# STM_Preamplifier.net
KiCad netlist of a schematic drawn in EasyEDA Pro
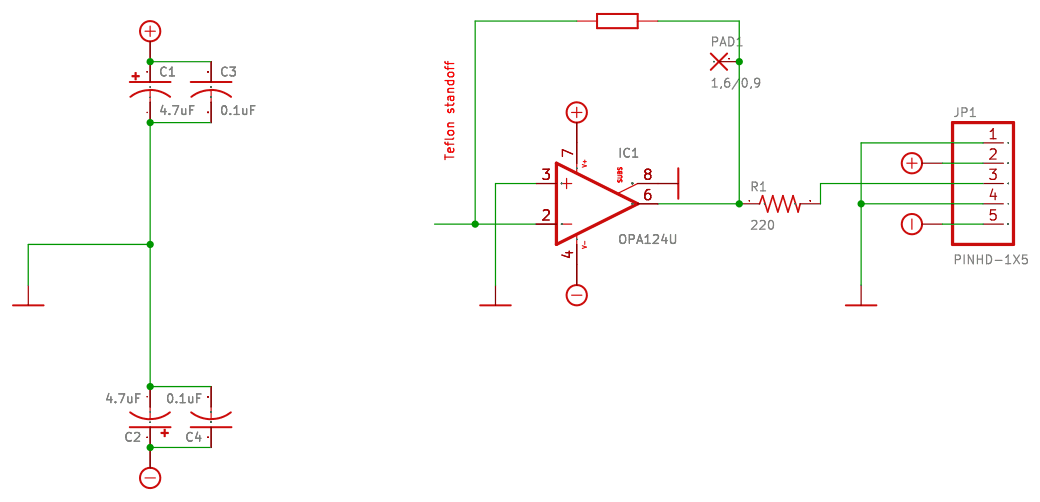
[diagram p0: schematic sheet]

(export (version "E")
  (design (tool "Eeschema 10.0.6"))
  (components
    (comp (ref "C1")
      (value "4.7uF")
      (footprint "easyedapro:C/6032-28W")
      (libsource (lib "easyedapro") (part "resistor_CPOL-US_C/6032-28W"))
    )
    (comp (ref "C2")
      (value "4.7uF")
      (footprint "easyedapro:C/6032-28W")
      (libsource (lib "easyedapro") (part "resistor_CPOL-US_C/6032-28W"))
    )
    (comp (ref "C3")
      (value "0.1uF")
      (footprint "easyedapro:C0603")
      (libsource (lib "easyedapro") (part "resistor_C-US_C0603"))
    )
    (comp (ref "C4")
      (value "0.1uF")
      (footprint "easyedapro:C0603")
      (libsource (lib "easyedapro") (part "resistor_C-US_C0603"))
    )
    (comp (ref "IC1")
      (value "OPA124U")
      (footprint "easyedapro:SO08")
      (libsource (lib "easyedapro") (part "burr-brown_OPA124U_"))
    )
    (comp (ref "JP1")
      (value "PINHD-1X5")
      (footprint "easyedapro:1X05")
      (libsource (lib "easyedapro") (part "pinhead_PINHD-1X5_"))
    )
    (comp (ref "PAD1")
      (value "1,6/0,9")
      (footprint "easyedapro:1,6/0,9")
      (libsource (lib "easyedapro") (part "wirepad_1,6/0,9_"))
    )
    (comp (ref "R1")
      (value "220")
      (footprint "easyedapro:R0603")
      (libsource (lib "easyedapro") (part "resistor_R-US__R0603"))
    )
    (comp (ref "R3") (value "100M") (libsource (lib "easyedapro") (part "docu-dummy_R_")))
  )
  (nets
    (net (code "1") (name "+9V") (class "Default")
      (node (ref "C1") (pin "+") (pinfunction "+_+") (pintype "unspecified"))
      (node (ref "C3") (pin "1") (pinfunction "1_1") (pintype "unspecified"))
      (node (ref "IC1") (pin "7") (pinfunction "V+_7") (pintype "unspecified"))
      (node (ref "JP1") (pin "2") (pinfunction "2_2") (pintype "unspecified"))
    )
    (net (code "2") (name "-9V") (class "Default")
      (node (ref "C2") (pin "+") (pinfunction "+_+") (pintype "unspecified"))
      (node (ref "C4") (pin "1") (pinfunction "1_1") (pintype "unspecified"))
      (node (ref "IC1") (pin "4") (pinfunction "V-_4") (pintype "unspecified"))
      (node (ref "JP1") (pin "5") (pinfunction "5_5") (pintype "unspecified"))
    )
    (net (code "3") (name "GND") (class "Default")
      (node (ref "C1") (pin "-") (pinfunction "-_-") (pintype "unspecified"))
      (node (ref "C2") (pin "-") (pinfunction "-_-") (pintype "unspecified"))
      (node (ref "C3") (pin "2") (pinfunction "2_2") (pintype "unspecified"))
      (node (ref "C4") (pin "2") (pinfunction "2_2") (pintype "unspecified"))
      (node (ref "IC1") (pin "3") (pinfunction "+IN_3") (pintype "input"))
      (node (ref "IC1") (pin "8") (pinfunction "SUBS_8") (pintype "unspecified"))
      (node (ref "JP1") (pin "1") (pinfunction "1_1") (pintype "unspecified"))
      (node (ref "JP1") (pin "4") (pinfunction "4_4") (pintype "unspecified"))
    )
    (net (code "4") (name "Net-(IC1-OUT)") (class "Default")
      (node (ref "IC1") (pin "6") (pinfunction "OUT_6") (pintype "output"))
      (node (ref "PAD1") (pin "1") (pinfunction "P_1") (pintype "unspecified"))
      (node (ref "R1") (pin "1") (pinfunction "1_1") (pintype "unspecified"))
    )
    (net (code "5") (name "Net-(JP1-Pad3)") (class "Default")
      (node (ref "JP1") (pin "3") (pinfunction "3_3") (pintype "unspecified"))
      (node (ref "R1") (pin "2") (pinfunction "2_2") (pintype "unspecified"))
    )
    (net (code "6") (name "unconnected-(IC1--IN-Pad2)") (class "Default")
      (node (ref "IC1") (pin "2") (pinfunction "-IN_2") (pintype "input"))
    )
  )
)
